# Power.net
KiCad netlist of a schematic drawn in Altium Designer
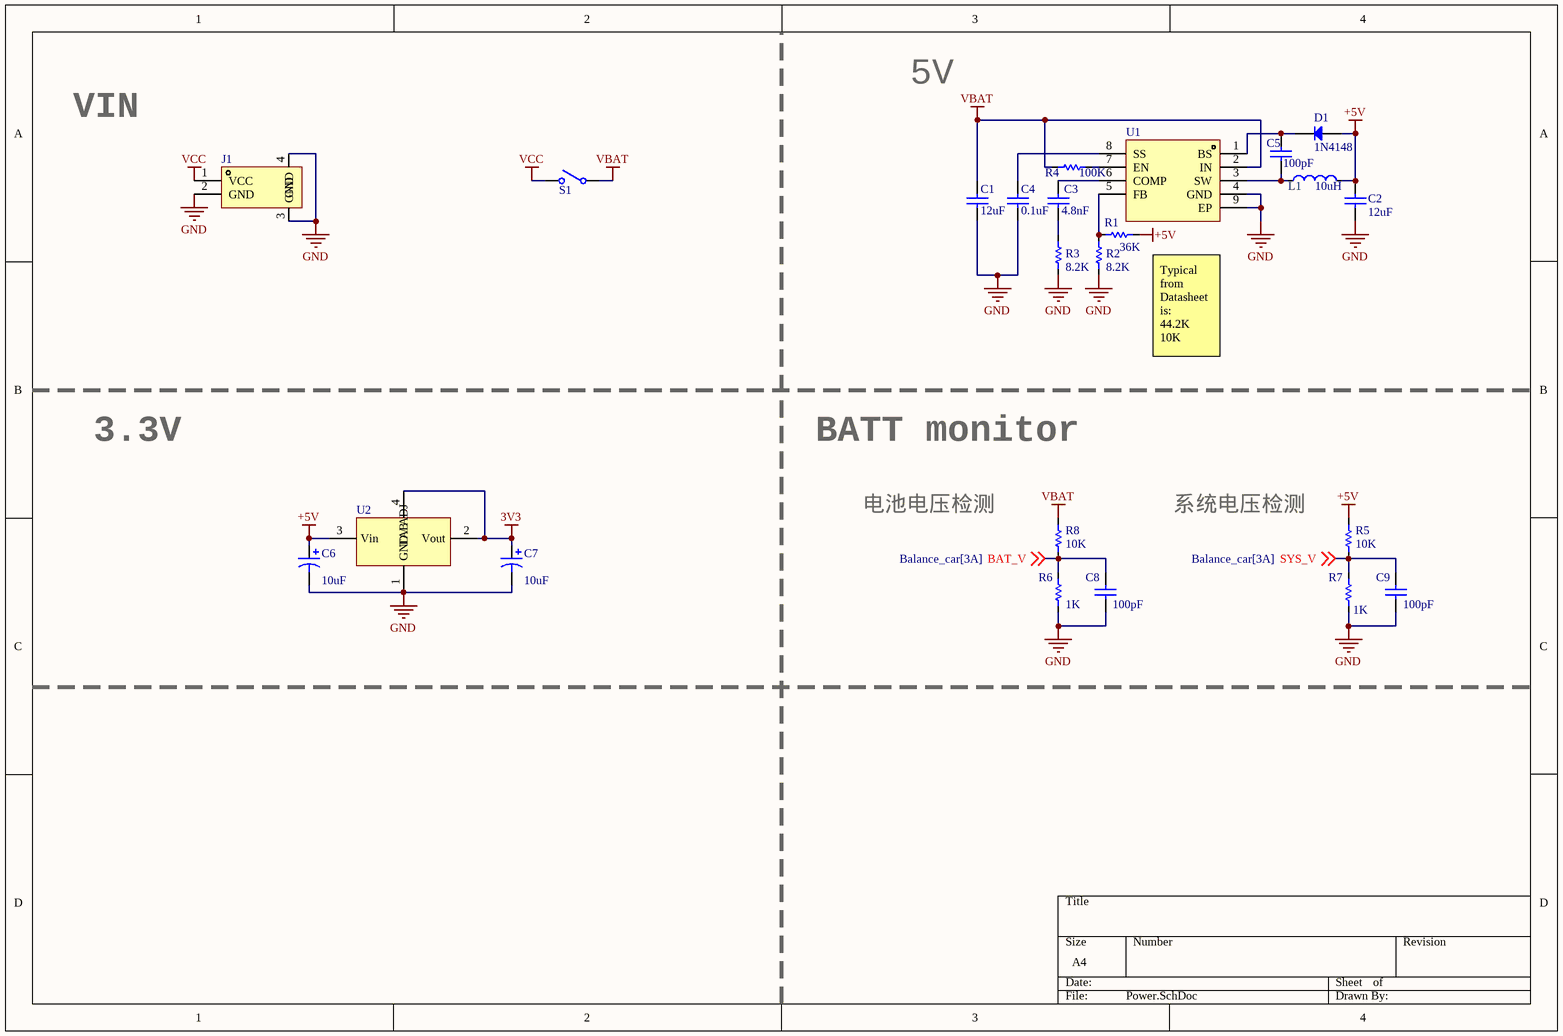
[diagram p0: Power.SchDoc]

(export (version "E")
  (design (tool "Eeschema 10.0.6"))
  (components
    (comp (ref "C1")
      (value "12uF")
      (footprint "C1206")
      (description "Capacitor")
      (fields (field (name "Comment") "Cap") (field (name "PUBLISHER") "Altium Limited"))
      (libsource (lib "Component footprints") (part "Cap"))
    )
    (comp (ref "C2")
      (value "12uF")
      (footprint "C1206")
      (description "Capacitor")
      (fields (field (name "Comment") "Cap") (field (name "PUBLISHER") "Altium Limited"))
      (libsource (lib "Component footprints") (part "Cap"))
    )
    (comp (ref "C3")
      (value "4.8nF")
      (footprint "C0603")
      (description "Capacitor")
      (fields (field (name "Comment") "Cap") (field (name "PUBLISHER") "Altium Limited"))
      (libsource (lib "Component footprints") (part "Cap"))
    )
    (comp (ref "C4")
      (value "0.1uF")
      (footprint "C0603")
      (description "Capacitor")
      (fields (field (name "Comment") "Cap") (field (name "PUBLISHER") "Altium Limited"))
      (libsource (lib "Component footprints") (part "Cap"))
    )
    (comp (ref "C5")
      (value "100pF")
      (footprint "C0603")
      (description "Capacitor")
      (fields (field (name "Comment") "Cap") (field (name "PUBLISHER") "Altium Limited"))
      (libsource (lib "Component footprints") (part "Cap"))
    )
    (comp (ref "C6")
      (value "10uF")
      (footprint "CAP-SMD_BD4.0-L4.3-W4.3-FD-LS5.3")
      (description "Polarized Capacitor (Axial)")
      (fields (field (name "Comment") "Cap Pol") (field (name "PUBLISHER") "Altium Limited"))
      (libsource (lib "Component footprints") (part "Cap Pol"))
    )
    (comp (ref "C7")
      (value "10uF")
      (footprint "CAP-SMD_BD4.0-L4.3-W4.3-FD-LS5.3")
      (description "Polarized Capacitor (Axial)")
      (fields (field (name "Comment") "Cap Pol") (field (name "PUBLISHER") "Altium Limited"))
      (libsource (lib "Component footprints") (part "Cap Pol"))
    )
    (comp (ref "C8")
      (value "100pF")
      (footprint "C0603")
      (description "Capacitor")
      (fields (field (name "Comment") "Cap") (field (name "PUBLISHER") "Altium Limited"))
      (libsource (lib "Component footprints") (part "Cap"))
    )
    (comp (ref "C9")
      (value "100pF")
      (footprint "C0603")
      (description "Capacitor")
      (fields (field (name "Comment") "Cap") (field (name "PUBLISHER") "Altium Limited"))
      (libsource (lib "Component footprints") (part "Cap"))
    )
    (comp (ref "D1")
      (value "1N4148")
      (footprint "SOD-123F")
      (description "High Conductance Fast Diode")
      (fields (field (name "PUBLISHER") "Altium Limited"))
      (libsource (lib "Component footprints") (part "1N4148"))
    )
    (comp (ref "J1")
      (value "XT60PW-M")
      (footprint "XT60PW-M")
      (libsource (lib "Connectivity_Plugs") (part "XT60PW-M"))
    )
    (comp (ref "L1")
      (value "10uH")
      (footprint "Component footprints:IND-SMD_L7.3-W6.6")
      (description "电感值:10uH;精度:±20%;额定电流:4A;饱和电流(Isat):5.5A;直流电阻(DCR):62mΩ;")
      (fields (field (name "MANUFACTURER") "PSA(信昌电陶)") (field (name "MANUFACTURER PART") "MCS0630-100MPY1"))
      (libsource (lib "Component footprints") (part "IND-SMD_L7.3-W6.6"))
    )
    (comp (ref "R1")
      (value "36K")
      (footprint "R0402")
      (description "Resistor")
      (fields (field (name "Comment") "Res") (field (name "PUBLISHER") "Altium Limited"))
      (libsource (lib "Component footprints") (part "Res"))
    )
    (comp (ref "R2")
      (value "8.2K")
      (footprint "R0402")
      (description "Resistor")
      (fields (field (name "Comment") "Res") (field (name "PUBLISHER") "Altium Limited"))
      (libsource (lib "Component footprints") (part "Res"))
    )
    (comp (ref "R3")
      (value "8.2K")
      (footprint "R0603")
      (description "Resistor")
      (fields (field (name "Comment") "Res") (field (name "PUBLISHER") "Altium Limited"))
      (libsource (lib "Component footprints") (part "Res"))
    )
    (comp (ref "R4")
      (value "100K")
      (footprint "R0603")
      (description "Resistor")
      (fields (field (name "Comment") "Res") (field (name "PUBLISHER") "Altium Limited"))
      (libsource (lib "Component footprints") (part "Res"))
    )
    (comp (ref "R5")
      (value "10K")
      (footprint "R0402")
      (description "Resistor")
      (fields (field (name "Comment") "Res") (field (name "PUBLISHER") "Altium Limited"))
      (libsource (lib "Component footprints") (part "Res"))
    )
    (comp (ref "R6")
      (value "1K")
      (footprint "R0402")
      (description "Resistor")
      (fields (field (name "Comment") "Res") (field (name "PUBLISHER") "Altium Limited"))
      (libsource (lib "Component footprints") (part "Res"))
    )
    (comp (ref "R7")
      (value "1K")
      (footprint "R0402")
      (description "Resistor")
      (fields (field (name "Comment") "Res") (field (name "PUBLISHER") "Altium Limited"))
      (libsource (lib "Component footprints") (part "Res"))
    )
    (comp (ref "R8")
      (value "10K")
      (footprint "R0402")
      (description "Resistor")
      (fields (field (name "Comment") "Res") (field (name "PUBLISHER") "Altium Limited"))
      (libsource (lib "Component footprints") (part "Res"))
    )
    (comp (ref "S1")
      (value "SW-PB")
      (footprint "SW-PB")
      (description "船型开关")
      (fields (field (name "PUBLISHER") "Altium Limited"))
      (libsource (lib "Common_Modules") (part "SW-PB"))
    )
    (comp (ref "U1") (value "MP2307") (footprint "MP2307") (libsource (lib "Power_Module") (part "MP2307")))
    (comp (ref "U2") (value "1117") (footprint "SOT-223-3") (libsource (lib "Power_Module") (part "1117")))
  )
  (nets
    (net (code "1") (name "+5V") (class "Default")
      (node (ref "C2") (pin "1") (pinfunction "1_1") (pintype "passive"))
      (node (ref "C6") (pin "1") (pinfunction "1_1") (pintype "passive"))
      (node (ref "D1") (pin "2") (pinfunction "A_2") (pintype "passive"))
      (node (ref "L1") (pin "2") (pinfunction "2_2") (pintype "passive"))
      (node (ref "R1") (pin "1") (pinfunction "1_1") (pintype "passive"))
      (node (ref "R5") (pin "1") (pinfunction "1_1") (pintype "passive"))
      (node (ref "U2") (pin "3") (pinfunction "Vin_3") (pintype "passive"))
    )
    (net (code "2") (name "3V3") (class "Default")
      (node (ref "C7") (pin "1") (pinfunction "1_1") (pintype "passive"))
      (node (ref "U2") (pin "2") (pinfunction "Vout_2") (pintype "passive"))
      (node (ref "U2") (pin "4") (pinfunction "TAB_4") (pintype "passive"))
    )
    (net (code "3") (name "BAT_V") (class "Default")
      (node (ref "C8") (pin "1") (pinfunction "1_1") (pintype "passive"))
      (node (ref "R6") (pin "1") (pinfunction "1_1") (pintype "passive"))
      (node (ref "R8") (pin "2") (pinfunction "2_2") (pintype "passive"))
    )
    (net (code "4") (name "GND") (class "Default")
      (node (ref "C1") (pin "1") (pinfunction "1_1") (pintype "passive"))
      (node (ref "C2") (pin "2") (pinfunction "2_2") (pintype "passive"))
      (node (ref "C4") (pin "1") (pinfunction "1_1") (pintype "passive"))
      (node (ref "C6") (pin "2") (pinfunction "2_2") (pintype "passive"))
      (node (ref "C7") (pin "2") (pinfunction "2_2") (pintype "passive"))
      (node (ref "C8") (pin "2") (pinfunction "2_2") (pintype "passive"))
      (node (ref "C9") (pin "2") (pinfunction "2_2") (pintype "passive"))
      (node (ref "J1") (pin "2") (pinfunction "GND_2") (pintype "passive"))
      (node (ref "J1") (pin "3") (pinfunction "GND_3") (pintype "passive"))
      (node (ref "J1") (pin "4") (pinfunction "GND_4") (pintype "passive"))
      (node (ref "R2") (pin "1") (pinfunction "1_1") (pintype "passive"))
      (node (ref "R3") (pin "1") (pinfunction "1_1") (pintype "passive"))
      (node (ref "R6") (pin "2") (pinfunction "2_2") (pintype "passive"))
      (node (ref "R7") (pin "2") (pinfunction "2_2") (pintype "passive"))
      (node (ref "U1") (pin "4") (pinfunction "GND_4") (pintype "passive"))
      (node (ref "U1") (pin "9") (pinfunction "EP_9") (pintype "passive"))
      (node (ref "U2") (pin "1") (pinfunction "GND_/_ADJ_1") (pintype "passive"))
    )
    (net (code "5") (name "Net-(C3-Pad1)") (class "Default")
      (node (ref "C3") (pin "1") (pinfunction "1_1") (pintype "passive"))
      (node (ref "R3") (pin "2") (pinfunction "2_2") (pintype "passive"))
    )
    (net (code "6") (name "Net-(D1-K)") (class "Default")
      (node (ref "C5") (pin "2") (pinfunction "2_2") (pintype "passive"))
      (node (ref "D1") (pin "1") (pinfunction "K_1") (pintype "passive"))
      (node (ref "U1") (pin "1") (pinfunction "BS_1") (pintype "passive"))
    )
    (net (code "7") (name "Net-(U1-COMP)") (class "Default")
      (node (ref "C3") (pin "2") (pinfunction "2_2") (pintype "passive"))
      (node (ref "U1") (pin "6") (pinfunction "COMP_6") (pintype "passive"))
    )
    (net (code "8") (name "Net-(U1-EN)") (class "Default")
      (node (ref "R4") (pin "2") (pinfunction "2_2") (pintype "passive"))
      (node (ref "U1") (pin "7") (pinfunction "EN_7") (pintype "passive"))
    )
    (net (code "9") (name "Net-(U1-FB)") (class "Default")
      (node (ref "R1") (pin "2") (pinfunction "2_2") (pintype "passive"))
      (node (ref "R2") (pin "2") (pinfunction "2_2") (pintype "passive"))
      (node (ref "U1") (pin "5") (pinfunction "FB_5") (pintype "passive"))
    )
    (net (code "10") (name "Net-(U1-SS)") (class "Default")
      (node (ref "C4") (pin "2") (pinfunction "2_2") (pintype "passive"))
      (node (ref "U1") (pin "8") (pinfunction "SS_8") (pintype "passive"))
    )
    (net (code "11") (name "Net-(U1-SW)") (class "Default")
      (node (ref "C5") (pin "1") (pinfunction "1_1") (pintype "passive"))
      (node (ref "L1") (pin "1") (pinfunction "1_1") (pintype "passive"))
      (node (ref "U1") (pin "3") (pinfunction "SW_3") (pintype "passive"))
    )
    (net (code "12") (name "SYS_V") (class "Default")
      (node (ref "C9") (pin "1") (pinfunction "1_1") (pintype "passive"))
      (node (ref "R5") (pin "2") (pinfunction "2_2") (pintype "passive"))
      (node (ref "R7") (pin "1") (pinfunction "1_1") (pintype "passive"))
    )
    (net (code "13") (name "VBAT") (class "Default")
      (node (ref "C1") (pin "2") (pinfunction "2_2") (pintype "passive"))
      (node (ref "R4") (pin "1") (pinfunction "1_1") (pintype "passive"))
      (node (ref "R8") (pin "1") (pinfunction "1_1") (pintype "passive"))
      (node (ref "S1") (pin "1") (pinfunction "COMMON_1") (pintype "passive"))
      (node (ref "U1") (pin "2") (pinfunction "IN_2") (pintype "passive"))
    )
    (net (code "14") (name "VCC") (class "Default")
      (node (ref "J1") (pin "1") (pinfunction "VCC_1") (pintype "passive"))
      (node (ref "S1") (pin "2") (pinfunction "NO_2") (pintype "passive"))
    )
  )
)
